# Sheet1.net
KiCad netlist of a schematic drawn in Altium Designer
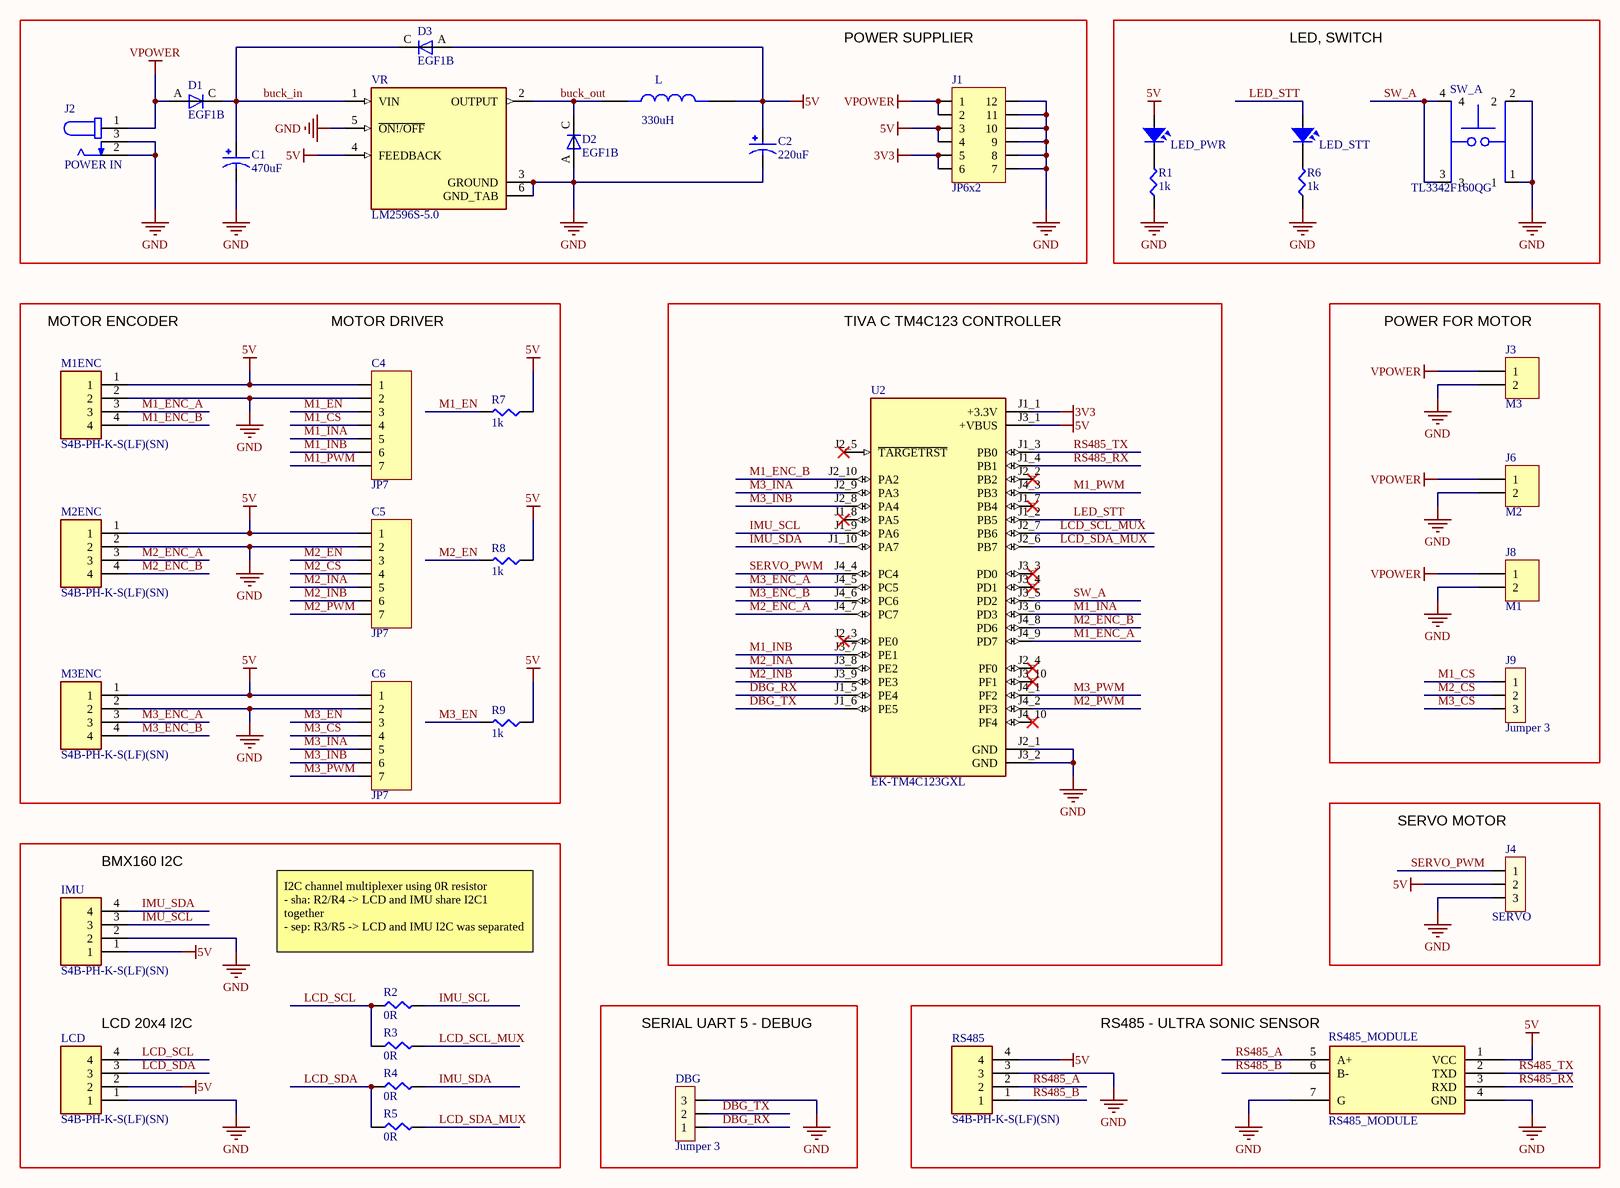
[diagram p0: Sheet1.SchDoc]

(export (version "E")
  (design (tool "Eeschema 10.0.6"))
  (components
    (comp (ref "C1")
      (value "470uF")
      (footprint "CAP_EEE2AA220P")
      (description "Capacitor; Alum Electrolytic; Cap 22 uF; Tol 20%; Vol-Rtg 100 VDC; SMT; 10x10.5; TR")
      (fields (field (name "MF") "Panasonic") (field (name "MP") "EEE-2AA220P"))
      (libsource (lib "EEE2AA220P") (part "EEE2AA220P"))
    )
    (comp (ref "C2")
      (value "220uF")
      (footprint "CAP_EEEHB1V220P")
      (description "EEE-HB Series 35 V 22 uF Ã˜ 6.3 x 5.8 mm 105 Â°C SMT V-Chip Aluminum Electrolytic")
      (fields (field (name "MP") "EEEHB1V220P") (field (name "MF") "Panasonic"))
      (libsource (lib "EEEHB1V220P") (part "EEEHB1V220P"))
    )
    (comp (ref "C4")
      (value "JP7")
      (footprint "JP7-C1T")
      (description "WR-PHD 2.54 mm Angled Socket Header")
      (fields
        (field (name "MANUFACTURER") "Würth Elektronik eiSos GmbH")
        (field (name "PARTNO") "613007143121")
        (field (name "CREATED BY") "Karrer Zheng")
      )
      (libsource (lib "My Library") (part "JP7_1"))
    )
    (comp (ref "C5")
      (value "JP7")
      (footprint "JP7-C1T")
      (description "WR-PHD 2.54 mm Angled Socket Header")
      (fields
        (field (name "MANUFACTURER") "Würth Elektronik eiSos GmbH")
        (field (name "PARTNO") "613007143121")
        (field (name "CREATED BY") "Karrer Zheng")
      )
      (libsource (lib "My Library") (part "JP7_1"))
    )
    (comp (ref "C6")
      (value "JP7")
      (footprint "JP7-C1T")
      (description "WR-PHD 2.54 mm Angled Socket Header")
      (fields
        (field (name "MANUFACTURER") "Würth Elektronik eiSos GmbH")
        (field (name "PARTNO") "613007143121")
        (field (name "CREATED BY") "Karrer Zheng")
      )
      (libsource (lib "My Library") (part "JP7_1"))
    )
    (comp (ref "D1")
      (value "EGF1B")
      (footprint "DIOM449X264X300L114X135N")
      (description "SS54 SMA\r\nDiode Shotky SS54 1N5824 5A 40V")
      (fields (field (name "MF") "ON Semiconductor"))
      (libsource (lib "EGF1B") (part "EGF1B"))
    )
    (comp (ref "D2")
      (value "EGF1B")
      (footprint "DIOM449X264X300L114X135N")
      (description "SS54 SMA\r\nDiode Shotky SS54 1N5824 5A 40V")
      (fields (field (name "MF") "ON Semiconductor"))
      (libsource (lib "EGF1B") (part "EGF1B"))
    )
    (comp (ref "D3")
      (value "EGF1B")
      (footprint "DIOM449X264X300L114X135N")
      (description "SS54 SMA\r\nDiode Shotky SS54 1N5824 5A 40V")
      (fields (field (name "MF") "ON Semiconductor"))
      (libsource (lib "EGF1B") (part "EGF1B"))
    )
    (comp (ref "DBG") (value "Jumper 3") (footprint "JP3") (libsource (lib "") (part "JP3_1")))
    (comp (ref "IMU")
      (value "S4B-PH-K-S(LF)(SN)")
      (footprint "JST_S4B-PH-K-S(LF)(SN)")
      (description "Connector Header Through Hole, Right Angle 4 position 0.079 _2.00mm_")
      (fields (field (name "MP") "S4B-PH-K-S_LF__SN_") (field (name "MF") "JST Sales"))
      (libsource (lib "S4B-PH-K-S_LF__SN_") (part "S4B-PH-K-S(LF)(SN)"))
    )
    (comp (ref "J1")
      (value "JP6x2")
      (footprint "JP6-D2T")
      (description "WR-PHD 2.54 mm Dual Socket Header")
      (fields
        (field (name "MANUFACTURER") "Würth Elektronik eiSos GmbH")
        (field (name "PARTNO") "61301221821")
        (field (name "CREATED BY") "Karrer Zheng")
      )
      (libsource (lib "My Library") (part "JP6x2"))
    )
    (comp (ref "J2")
      (value "POWER IN")
      (footprint "CUI_PJ-002B")
      (description "2.5 x 6.5 mm, 2.5 A, Horizontal, Through Hole, Dc Power Jack Connector")
      (fields (field (name "MF") "CUI Devices") (field (name "MP") "PJ-002B"))
      (libsource (lib "PJ-002B") (part "PJ-002B"))
    )
    (comp (ref "J3")
      (value "M3")
      (footprint "KF2-5.08")
      (fields
        (field (name "MANUFACTURER") "Würth Elektronik eiSos GmbH")
        (field (name "PARTNO") "691103110002")
        (field (name "CREATED BY") "Karrer Zheng")
      )
      (libsource (lib "My Library") (part "KF2"))
    )
    (comp (ref "J4") (value "SERVO") (footprint "JP3") (libsource (lib "My Library") (part "JP3")))
    (comp (ref "J6")
      (value "M2")
      (footprint "KF2-5.08")
      (fields
        (field (name "MANUFACTURER") "Würth Elektronik eiSos GmbH")
        (field (name "PARTNO") "691103110002")
        (field (name "CREATED BY") "Karrer Zheng")
      )
      (libsource (lib "My Library") (part "KF2"))
    )
    (comp (ref "J8")
      (value "M1")
      (footprint "KF2-5.08")
      (fields
        (field (name "MANUFACTURER") "Würth Elektronik eiSos GmbH")
        (field (name "PARTNO") "691103110002")
        (field (name "CREATED BY") "Karrer Zheng")
      )
      (libsource (lib "My Library") (part "KF2"))
    )
    (comp (ref "J9") (value "Jumper 3") (footprint "JP3") (libsource (lib "My Library") (part "JP3")))
    (comp (ref "L")
      (value "330uH")
      (footprint "IND_B1047AS-331M=P3")
      (description "Inductor with Inductance: 330uH Tol. +/-20%, Package: 2929 (7373)")
      (fields (field (name "MF") "Murata") (field (name "MP") "B1047AS-331M=P3"))
      (libsource (lib "B1047AS-331M_P3") (part "B1047AS-331M=P3"))
    )
    (comp (ref "LCD")
      (value "S4B-PH-K-S(LF)(SN)")
      (footprint "JST_S4B-PH-K-S(LF)(SN)")
      (description "Connector Header Through Hole, Right Angle 4 position 0.079 _2.00mm_")
      (fields (field (name "MP") "S4B-PH-K-S_LF__SN_") (field (name "MF") "JST Sales"))
      (libsource (lib "S4B-PH-K-S_LF__SN_") (part "S4B-PH-K-S(LF)(SN)"))
    )
    (comp (ref "LED_PWR")
      (value "PWR LED")
      (footprint "LED-0805-Green")
      (libsource (lib "My Library") (part "LED SMD"))
    )
    (comp (ref "LED_STT")
      (value "LED")
      (footprint "LED-0805-Green")
      (libsource (lib "My Library") (part "LED SMD"))
    )
    (comp (ref "M1ENC")
      (value "S4B-PH-K-S(LF)(SN)")
      (footprint "JST_S4B-PH-K-S(LF)(SN)")
      (description "Connector Header Through Hole, Right Angle 4 position 0.079 _2.00mm_")
      (fields (field (name "MP") "S4B-PH-K-S_LF__SN_") (field (name "MF") "JST Sales"))
      (libsource (lib "") (part "S4B-PH-K-S(LF)(SN)_1"))
    )
    (comp (ref "M2ENC")
      (value "S4B-PH-K-S(LF)(SN)")
      (footprint "JST_S4B-PH-K-S(LF)(SN)")
      (description "Connector Header Through Hole, Right Angle 4 position 0.079 _2.00mm_")
      (fields (field (name "MP") "S4B-PH-K-S_LF__SN_") (field (name "MF") "JST Sales"))
      (libsource (lib "") (part "S4B-PH-K-S(LF)(SN)_1"))
    )
    (comp (ref "M3ENC")
      (value "S4B-PH-K-S(LF)(SN)")
      (footprint "JST_S4B-PH-K-S(LF)(SN)")
      (description "Connector Header Through Hole, Right Angle 4 position 0.079 _2.00mm_")
      (fields (field (name "MP") "S4B-PH-K-S_LF__SN_") (field (name "MF") "JST Sales"))
      (libsource (lib "") (part "S4B-PH-K-S(LF)(SN)_1"))
    )
    (comp (ref "R1")
      (value "1k")
      (footprint "SMD-0805-RES")
      (description "RES SMD 0805")
      (fields (field (name "PART NUMBER") "ERJ-S6SJR20V") (field (name "DIGI-KEY PART NUMBER") "P.2BKCT-ND"))
      (libsource (lib "Panasonic_ERJ_0805") (part "Res SMD 0805"))
    )
    (comp (ref "R2")
      (value "0R")
      (footprint "SMD-0805-RES")
      (description "RES SMD 0805")
      (fields (field (name "PART NUMBER") "ERJ-S6SJR20V") (field (name "DIGI-KEY PART NUMBER") "P.2BKCT-ND"))
      (libsource (lib "Panasonic_ERJ_0805") (part "Res SMD 0805"))
    )
    (comp (ref "R3")
      (value "0R")
      (footprint "SMD-0805-RES")
      (description "RES SMD 0805")
      (fields (field (name "PART NUMBER") "ERJ-S6SJR20V") (field (name "DIGI-KEY PART NUMBER") "P.2BKCT-ND"))
      (libsource (lib "Panasonic_ERJ_0805") (part "Res SMD 0805"))
    )
    (comp (ref "R4")
      (value "0R")
      (footprint "SMD-0805-RES")
      (description "RES SMD 0805")
      (fields (field (name "PART NUMBER") "ERJ-S6SJR20V") (field (name "DIGI-KEY PART NUMBER") "P.2BKCT-ND"))
      (libsource (lib "Panasonic_ERJ_0805") (part "Res SMD 0805"))
    )
    (comp (ref "R5")
      (value "0R")
      (footprint "SMD-0805-RES")
      (description "RES SMD 0805")
      (fields (field (name "PART NUMBER") "ERJ-S6SJR20V") (field (name "DIGI-KEY PART NUMBER") "P.2BKCT-ND"))
      (libsource (lib "Panasonic_ERJ_0805") (part "Res SMD 0805"))
    )
    (comp (ref "R6")
      (value "1k")
      (footprint "SMD-0805-RES")
      (description "RES SMD 0805")
      (fields (field (name "PART NUMBER") "ERJ-S6SJR20V") (field (name "DIGI-KEY PART NUMBER") "P.2BKCT-ND"))
      (libsource (lib "Panasonic_ERJ_0805") (part "Res SMD 0805"))
    )
    (comp (ref "R7")
      (value "1k")
      (footprint "SMD-0805-RES")
      (description "RES SMD 0805")
      (fields (field (name "PART NUMBER") "ERJ-S6SJR20V") (field (name "DIGI-KEY PART NUMBER") "P.2BKCT-ND"))
      (libsource (lib "Panasonic_ERJ_0805") (part "Res SMD 0805"))
    )
    (comp (ref "R8")
      (value "1k")
      (footprint "SMD-0805-RES")
      (description "RES SMD 0805")
      (fields (field (name "PART NUMBER") "ERJ-S6SJR20V") (field (name "DIGI-KEY PART NUMBER") "P.2BKCT-ND"))
      (libsource (lib "Panasonic_ERJ_0805") (part "Res SMD 0805"))
    )
    (comp (ref "R9")
      (value "1k")
      (footprint "SMD-0805-RES")
      (description "RES SMD 0805")
      (fields (field (name "PART NUMBER") "ERJ-S6SJR20V") (field (name "DIGI-KEY PART NUMBER") "P.2BKCT-ND"))
      (libsource (lib "Panasonic_ERJ_0805") (part "Res SMD 0805"))
    )
    (comp (ref "RS485")
      (value "S4B-PH-K-S(LF)(SN)")
      (footprint "JST_S4B-PH-K-S(LF)(SN)")
      (description "Connector Header Through Hole, Right Angle 4 position 0.079 _2.00mm_")
      (fields (field (name "MP") "S4B-PH-K-S_LF__SN_") (field (name "MF") "JST Sales"))
      (libsource (lib "S4B-PH-K-S_LF__SN_") (part "S4B-PH-K-S(LF)(SN)"))
    )
    (comp (ref "RS485_MODULE")
      (value "RS485_MODULE")
      (footprint "RS485_MODULE")
      (libsource (lib "custom_lib") (part "RS485_MODULE"))
    )
    (comp (ref "SW_A")
      (value "TL3342F160QG")
      (footprint "SW_TL3342F160QG")
      (description "Tactile Switch SPST-NO Top Actuated Surface Mount")
      (fields (field (name "MF") "E-Switch"))
      (libsource (lib "TL3342F160QG") (part "TL3342F160QG"))
    )
    (comp (ref "U2")
      (value "EK-TM4C123GXL")
      (footprint "MODULE_EK-TM4C123GXL")
      (description "ARMÂ® CortexÂ®-M4F Based MCU TM4C123G LaunchPadâ„¢ Evaluation Kit")
      (fields (field (name "MF") "Texas Instruments"))
      (libsource (lib "EK-TM4C123GXL") (part "EK-TM4C123GXL"))
    )
    (comp (ref "VR")
      (value "LM2596S-5.0")
      (footprint "TO170P1524X483-6N")
      (description "SIMPLE SWITCHER&reg; 4.5V to 40V, 3A Low Component Count Step-Down Regulator 5-DDPAK/TO-263")
      (fields (field (name "MF") "Texas Instruments") (field (name "MP") "LM2596S-5.0/NOPB"))
      (libsource (lib "LM2596S-5.0") (part "LM2596S-5.0"))
    )
  )
  (nets
    (net (code "1") (name "/DBG_RX") (class "Default")
      (node (ref "DBG") (pin "1") (pinfunction "1_1") (pintype "passive"))
      (node (ref "U2") (pin "J1_5") (pinfunction "PE4_J1_5") (pintype "bidirectional"))
    )
    (net (code "2") (name "/DBG_TX") (class "Default")
      (node (ref "DBG") (pin "2") (pinfunction "2_2") (pintype "passive"))
      (node (ref "U2") (pin "J1_6") (pinfunction "PE5_J1_6") (pintype "bidirectional"))
    )
    (net (code "3") (name "/IMU_SCL") (class "Default")
      (node (ref "IMU") (pin "3") (pinfunction "3_3") (pintype "passive"))
      (node (ref "R2") (pin "2") (pinfunction "2_2") (pintype "passive"))
      (node (ref "U2") (pin "J1_9") (pinfunction "PA6_J1_9") (pintype "bidirectional"))
    )
    (net (code "4") (name "/IMU_SDA") (class "Default")
      (node (ref "IMU") (pin "4") (pinfunction "4_4") (pintype "passive"))
      (node (ref "R4") (pin "2") (pinfunction "2_2") (pintype "passive"))
      (node (ref "U2") (pin "J1_10") (pinfunction "PA7_J1_10") (pintype "bidirectional"))
    )
    (net (code "5") (name "/LCD_SCL") (class "Default")
      (node (ref "LCD") (pin "4") (pinfunction "4_4") (pintype "passive"))
      (node (ref "R2") (pin "1") (pinfunction "1_1") (pintype "passive"))
      (node (ref "R3") (pin "1") (pinfunction "1_1") (pintype "passive"))
    )
    (net (code "6") (name "/LCD_SCL_MUX") (class "Default")
      (node (ref "R3") (pin "2") (pinfunction "2_2") (pintype "passive"))
      (node (ref "U2") (pin "J2_7") (pinfunction "PB6_J2_7") (pintype "bidirectional"))
    )
    (net (code "7") (name "/LCD_SDA") (class "Default")
      (node (ref "LCD") (pin "3") (pinfunction "3_3") (pintype "passive"))
      (node (ref "R4") (pin "1") (pinfunction "1_1") (pintype "passive"))
      (node (ref "R5") (pin "1") (pinfunction "1_1") (pintype "passive"))
    )
    (net (code "8") (name "/LCD_SDA_MUX") (class "Default")
      (node (ref "R5") (pin "2") (pinfunction "2_2") (pintype "passive"))
      (node (ref "U2") (pin "J2_6") (pinfunction "PB7_J2_6") (pintype "bidirectional"))
    )
    (net (code "9") (name "/LED_STT") (class "Default")
      (node (ref "LED_STT") (pin "1") (pinfunction "1_1") (pintype "passive"))
      (node (ref "U2") (pin "J1_2") (pinfunction "PB5_J1_2") (pintype "bidirectional"))
    )
    (net (code "10") (name "/M1_CS") (class "Default")
      (node (ref "C4") (pin "4") (pinfunction "4_4") (pintype "passive"))
      (node (ref "J9") (pin "1") (pinfunction "1_1") (pintype "passive"))
    )
    (net (code "11") (name "/M1_EN") (class "Default")
      (node (ref "C4") (pin "3") (pinfunction "3_3") (pintype "passive"))
      (node (ref "R7") (pin "2") (pinfunction "2_2") (pintype "passive"))
    )
    (net (code "12") (name "/M1_ENC_A") (class "Default")
      (node (ref "M1ENC") (pin "3") (pinfunction "3_3") (pintype "passive"))
      (node (ref "U2") (pin "J4_9") (pinfunction "PD7_J4_9") (pintype "bidirectional"))
    )
    (net (code "13") (name "/M1_ENC_B") (class "Default")
      (node (ref "M1ENC") (pin "4") (pinfunction "4_4") (pintype "passive"))
      (node (ref "U2") (pin "J2_10") (pinfunction "PA2_J2_10") (pintype "bidirectional"))
    )
    (net (code "14") (name "/M1_INA") (class "Default")
      (node (ref "C4") (pin "5") (pinfunction "5_5") (pintype "passive"))
      (node (ref "U2") (pin "J3_6") (pinfunction "PD3_J3_6") (pintype "bidirectional"))
    )
    (net (code "15") (name "/M1_INB") (class "Default")
      (node (ref "C4") (pin "6") (pinfunction "6_6") (pintype "passive"))
      (node (ref "U2") (pin "J3_7") (pinfunction "PE1_J3_7") (pintype "bidirectional"))
    )
    (net (code "16") (name "/M1_PWM") (class "Default")
      (node (ref "C4") (pin "7") (pinfunction "7_7") (pintype "passive"))
      (node (ref "U2") (pin "J4_3") (pinfunction "PB3_J4_3") (pintype "bidirectional"))
    )
    (net (code "17") (name "/M2_CS") (class "Default")
      (node (ref "C5") (pin "4") (pinfunction "4_4") (pintype "passive"))
      (node (ref "J9") (pin "2") (pinfunction "2_2") (pintype "passive"))
    )
    (net (code "18") (name "/M2_EN") (class "Default")
      (node (ref "C5") (pin "3") (pinfunction "3_3") (pintype "passive"))
      (node (ref "R8") (pin "2") (pinfunction "2_2") (pintype "passive"))
    )
    (net (code "19") (name "/M2_ENC_A") (class "Default")
      (node (ref "M2ENC") (pin "3") (pinfunction "3_3") (pintype "passive"))
      (node (ref "U2") (pin "J4_7") (pinfunction "PC7_J4_7") (pintype "bidirectional"))
    )
    (net (code "20") (name "/M2_ENC_B") (class "Default")
      (node (ref "M2ENC") (pin "4") (pinfunction "4_4") (pintype "passive"))
      (node (ref "U2") (pin "J4_8") (pinfunction "PD6_J4_8") (pintype "bidirectional"))
    )
    (net (code "21") (name "/M2_INA") (class "Default")
      (node (ref "C5") (pin "5") (pinfunction "5_5") (pintype "passive"))
      (node (ref "U2") (pin "J3_8") (pinfunction "PE2_J3_8") (pintype "bidirectional"))
    )
    (net (code "22") (name "/M2_INB") (class "Default")
      (node (ref "C5") (pin "6") (pinfunction "6_6") (pintype "passive"))
      (node (ref "U2") (pin "J3_9") (pinfunction "PE3_J3_9") (pintype "bidirectional"))
    )
    (net (code "23") (name "/M2_PWM") (class "Default")
      (node (ref "C5") (pin "7") (pinfunction "7_7") (pintype "passive"))
      (node (ref "U2") (pin "J4_2") (pinfunction "PF3_J4_2") (pintype "bidirectional"))
    )
    (net (code "24") (name "/M3_CS") (class "Default")
      (node (ref "C6") (pin "4") (pinfunction "4_4") (pintype "passive"))
      (node (ref "J9") (pin "3") (pinfunction "3_3") (pintype "passive"))
    )
    (net (code "25") (name "/M3_EN") (class "Default")
      (node (ref "C6") (pin "3") (pinfunction "3_3") (pintype "passive"))
      (node (ref "R9") (pin "2") (pinfunction "2_2") (pintype "passive"))
    )
    (net (code "26") (name "/M3_ENC_A") (class "Default")
      (node (ref "M3ENC") (pin "3") (pinfunction "3_3") (pintype "passive"))
      (node (ref "U2") (pin "J4_5") (pinfunction "PC5_J4_5") (pintype "bidirectional"))
    )
    (net (code "27") (name "/M3_ENC_B") (class "Default")
      (node (ref "M3ENC") (pin "4") (pinfunction "4_4") (pintype "passive"))
      (node (ref "U2") (pin "J4_6") (pinfunction "PC6_J4_6") (pintype "bidirectional"))
    )
    (net (code "28") (name "/M3_INA") (class "Default")
      (node (ref "C6") (pin "5") (pinfunction "5_5") (pintype "passive"))
      (node (ref "U2") (pin "J2_9") (pinfunction "PA3_J2_9") (pintype "bidirectional"))
    )
    (net (code "29") (name "/M3_INB") (class "Default")
      (node (ref "C6") (pin "6") (pinfunction "6_6") (pintype "passive"))
      (node (ref "U2") (pin "J2_8") (pinfunction "PA4_J2_8") (pintype "bidirectional"))
    )
    (net (code "30") (name "/M3_PWM") (class "Default")
      (node (ref "C6") (pin "7") (pinfunction "7_7") (pintype "passive"))
      (node (ref "U2") (pin "J4_1") (pinfunction "PF2_J4_1") (pintype "bidirectional"))
    )
    (net (code "31") (name "/RS485_A") (class "Default")
      (node (ref "RS485") (pin "2") (pinfunction "2_2") (pintype "passive"))
      (node (ref "RS485_MODULE") (pin "5") (pinfunction "A+_5") (pintype "passive"))
    )
    (net (code "32") (name "/RS485_B") (class "Default")
      (node (ref "RS485") (pin "1") (pinfunction "1_1") (pintype "passive"))
      (node (ref "RS485_MODULE") (pin "6") (pinfunction "B-_6") (pintype "passive"))
    )
    (net (code "33") (name "/RS485_RX") (class "Default")
      (node (ref "RS485_MODULE") (pin "3") (pinfunction "RXD_3") (pintype "passive"))
      (node (ref "U2") (pin "J1_4") (pinfunction "PB1_J1_4") (pintype "bidirectional"))
    )
    (net (code "34") (name "/RS485_TX") (class "Default")
      (node (ref "RS485_MODULE") (pin "2") (pinfunction "TXD_2") (pintype "passive"))
      (node (ref "U2") (pin "J1_3") (pinfunction "PB0_J1_3") (pintype "bidirectional"))
    )
    (net (code "35") (name "/SERVO_PWM") (class "Default")
      (node (ref "J4") (pin "1") (pinfunction "1_1") (pintype "passive"))
      (node (ref "U2") (pin "J4_4") (pinfunction "PC4_J4_4") (pintype "bidirectional"))
    )
    (net (code "36") (name "/SW_A") (class "Default")
      (node (ref "SW_A") (pin "3") (pinfunction "3_3") (pintype "passive"))
      (node (ref "SW_A") (pin "4") (pinfunction "4_4") (pintype "passive"))
      (node (ref "U2") (pin "J3_5") (pinfunction "PD2_J3_5") (pintype "bidirectional"))
    )
    (net (code "37") (name "/buck_in") (class "Default")
      (node (ref "C1") (pin "1") (pinfunction "1_1") (pintype "passive"))
      (node (ref "D1") (pin "C") (pinfunction "C_C") (pintype "passive"))
      (node (ref "D3") (pin "C") (pinfunction "C_C") (pintype "passive"))
      (node (ref "VR") (pin "1") (pinfunction "VIN_1") (pintype "input"))
    )
    (net (code "38") (name "/buck_out") (class "Default")
      (node (ref "D2") (pin "C") (pinfunction "C_C") (pintype "passive"))
      (node (ref "L") (pin "1") (pinfunction "1_1") (pintype "passive"))
      (node (ref "VR") (pin "2") (pinfunction "OUTPUT_2") (pintype "output"))
    )
    (net (code "39") (name "3V3") (class "Default")
      (node (ref "J1") (pin "5") (pinfunction "5_5") (pintype "passive"))
      (node (ref "J1") (pin "6") (pinfunction "6_6") (pintype "passive"))
      (node (ref "U2") (pin "J1_1") (pinfunction "+3.3V_J1_1") (pintype "power_in"))
    )
    (net (code "40") (name "5V") (class "Default")
      (node (ref "C2") (pin "1") (pinfunction "1_1") (pintype "passive"))
      (node (ref "C4") (pin "1") (pinfunction "1_1") (pintype "passive"))
      (node (ref "C5") (pin "1") (pinfunction "1_1") (pintype "passive"))
      (node (ref "C6") (pin "1") (pinfunction "1_1") (pintype "passive"))
      (node (ref "D3") (pin "A") (pinfunction "A_A") (pintype "passive"))
      (node (ref "IMU") (pin "1") (pinfunction "1_1") (pintype "passive"))
      (node (ref "J1") (pin "3") (pinfunction "3_3") (pintype "passive"))
      (node (ref "J1") (pin "4") (pinfunction "4_4") (pintype "passive"))
      (node (ref "J4") (pin "2") (pinfunction "2_2") (pintype "passive"))
      (node (ref "L") (pin "2") (pinfunction "2_2") (pintype "passive"))
      (node (ref "LCD") (pin "2") (pinfunction "2_2") (pintype "passive"))
      (node (ref "LED_PWR") (pin "1") (pinfunction "1_1") (pintype "passive"))
      (node (ref "M1ENC") (pin "1") (pinfunction "1_1") (pintype "passive"))
      (node (ref "M2ENC") (pin "1") (pinfunction "1_1") (pintype "passive"))
      (node (ref "M3ENC") (pin "1") (pinfunction "1_1") (pintype "passive"))
      (node (ref "R7") (pin "1") (pinfunction "1_1") (pintype "passive"))
      (node (ref "R8") (pin "1") (pinfunction "1_1") (pintype "passive"))
      (node (ref "R9") (pin "1") (pinfunction "1_1") (pintype "passive"))
      (node (ref "RS485") (pin "4") (pinfunction "4_4") (pintype "passive"))
      (node (ref "RS485_MODULE") (pin "1") (pinfunction "VCC_1") (pintype "passive"))
      (node (ref "U2") (pin "J3_1") (pinfunction "+VBUS_J3_1") (pintype "power_in"))
      (node (ref "VR") (pin "4") (pinfunction "FEEDBACK_4") (pintype "input"))
    )
    (net (code "41") (name "GND") (class "Default")
      (node (ref "C1") (pin "2") (pinfunction "2_2") (pintype "passive"))
      (node (ref "C2") (pin "2") (pinfunction "2_2") (pintype "passive"))
      (node (ref "C4") (pin "2") (pinfunction "2_2") (pintype "passive"))
      (node (ref "C5") (pin "2") (pinfunction "2_2") (pintype "passive"))
      (node (ref "C6") (pin "2") (pinfunction "2_2") (pintype "passive"))
      (node (ref "D2") (pin "A") (pinfunction "A_A") (pintype "passive"))
      (node (ref "DBG") (pin "3") (pinfunction "3_3") (pintype "passive"))
      (node (ref "IMU") (pin "2") (pinfunction "2_2") (pintype "passive"))
      (node (ref "J1") (pin "10") (pinfunction "10_10") (pintype "passive"))
      (node (ref "J1") (pin "11") (pinfunction "11_11") (pintype "passive"))
      (node (ref "J1") (pin "12") (pinfunction "12_12") (pintype "passive"))
      (node (ref "J1") (pin "7") (pinfunction "7_7") (pintype "passive"))
      (node (ref "J1") (pin "8") (pinfunction "8_8") (pintype "passive"))
      (node (ref "J1") (pin "9") (pinfunction "9_9") (pintype "passive"))
      (node (ref "J2") (pin "2") (pinfunction "2_2") (pintype "passive"))
      (node (ref "J2") (pin "3") (pinfunction "3_3") (pintype "passive"))
      (node (ref "J3") (pin "2") (pinfunction "2_2") (pintype "passive"))
      (node (ref "J4") (pin "3") (pinfunction "3_3") (pintype "passive"))
      (node (ref "J6") (pin "2") (pinfunction "2_2") (pintype "passive"))
      (node (ref "J8") (pin "2") (pinfunction "2_2") (pintype "passive"))
      (node (ref "LCD") (pin "1") (pinfunction "1_1") (pintype "passive"))
      (node (ref "M1ENC") (pin "2") (pinfunction "2_2") (pintype "passive"))
      (node (ref "M2ENC") (pin "2") (pinfunction "2_2") (pintype "passive"))
      (node (ref "M3ENC") (pin "2") (pinfunction "2_2") (pintype "passive"))
      (node (ref "R1") (pin "1") (pinfunction "1_1") (pintype "passive"))
      (node (ref "R6") (pin "1") (pinfunction "1_1") (pintype "passive"))
      (node (ref "RS485") (pin "3") (pinfunction "3_3") (pintype "passive"))
      (node (ref "RS485_MODULE") (pin "4") (pinfunction "GND_4") (pintype "passive"))
      (node (ref "RS485_MODULE") (pin "7") (pinfunction "G_7") (pintype "passive"))
      (node (ref "SW_A") (pin "1") (pinfunction "1_1") (pintype "passive"))
      (node (ref "SW_A") (pin "2") (pinfunction "2_2") (pintype "passive"))
      (node (ref "U2") (pin "J2_1") (pinfunction "GND_J2_1") (pintype "power_in"))
      (node (ref "U2") (pin "J3_2") (pinfunction "GND_J3_2") (pintype "power_in"))
      (node (ref "VR") (pin "3") (pinfunction "GROUND_3") (pintype "power_in"))
      (node (ref "VR") (pin "5") (pinfunction "~{ON!/OFF}_5") (pintype "input"))
      (node (ref "VR") (pin "6") (pinfunction "GND_TAB_6") (pintype "power_in"))
    )
    (net (code "42") (name "Net-(LED_PWR-Pad2)") (class "Default")
      (node (ref "LED_PWR") (pin "2") (pinfunction "2_2") (pintype "passive"))
      (node (ref "R1") (pin "2") (pinfunction "2_2") (pintype "passive"))
    )
    (net (code "43") (name "Net-(LED_STT-Pad2)") (class "Default")
      (node (ref "LED_STT") (pin "2") (pinfunction "2_2") (pintype "passive"))
      (node (ref "R6") (pin "2") (pinfunction "2_2") (pintype "passive"))
    )
    (net (code "44") (name "VPOWER") (class "Default")
      (node (ref "D1") (pin "A") (pinfunction "A_A") (pintype "passive"))
      (node (ref "J1") (pin "1") (pinfunction "1_1") (pintype "passive"))
      (node (ref "J1") (pin "2") (pinfunction "2_2") (pintype "passive"))
      (node (ref "J2") (pin "1") (pinfunction "1_1") (pintype "passive"))
      (node (ref "J3") (pin "1") (pinfunction "1_1") (pintype "passive"))
      (node (ref "J6") (pin "1") (pinfunction "1_1") (pintype "passive"))
      (node (ref "J8") (pin "1") (pinfunction "1_1") (pintype "passive"))
    )
    (net (code "45") (name "unconnected-(U2-PA5-PadJ1_8)") (class "Default")
      (node (ref "U2") (pin "J1_8") (pinfunction "PA5_J1_8") (pintype "bidirectional+no_connect"))
    )
    (net (code "46") (name "unconnected-(U2-PB2-PadJ2_2)") (class "Default")
      (node (ref "U2") (pin "J2_2") (pinfunction "PB2_J2_2") (pintype "bidirectional+no_connect"))
    )
    (net (code "47") (name "unconnected-(U2-PB4-PadJ1_7)") (class "Default")
      (node (ref "U2") (pin "J1_7") (pinfunction "PB4_J1_7") (pintype "bidirectional+no_connect"))
    )
    (net (code "48") (name "unconnected-(U2-PD0-PadJ3_3)") (class "Default")
      (node (ref "U2") (pin "J3_3") (pinfunction "PD0_J3_3") (pintype "bidirectional+no_connect"))
    )
    (net (code "49") (name "unconnected-(U2-PD1-PadJ3_4)") (class "Default")
      (node (ref "U2") (pin "J3_4") (pinfunction "PD1_J3_4") (pintype "bidirectional+no_connect"))
    )
    (net (code "50") (name "unconnected-(U2-PE0-PadJ2_3)") (class "Default")
      (node (ref "U2") (pin "J2_3") (pinfunction "PE0_J2_3") (pintype "bidirectional+no_connect"))
    )
    (net (code "51") (name "unconnected-(U2-PF0-PadJ2_4)") (class "Default")
      (node (ref "U2") (pin "J2_4") (pinfunction "PF0_J2_4") (pintype "bidirectional+no_connect"))
    )
    (net (code "52") (name "unconnected-(U2-PF1-PadJ3_10)") (class "Default")
      (node (ref "U2") (pin "J3_10") (pinfunction "PF1_J3_10") (pintype "bidirectional+no_connect"))
    )
    (net (code "53") (name "unconnected-(U2-PF4-PadJ4_10)") (class "Default")
      (node (ref "U2") (pin "J4_10") (pinfunction "PF4_J4_10") (pintype "bidirectional+no_connect"))
    )
    (net (code "54") (name "unconnected-(U2-~{TARGETRST}-PadJ2_5)") (class "Default")
      (node (ref "U2") (pin "J2_5") (pinfunction "~{TARGETRST}_J2_5") (pintype "input+no_connect"))
    )
  )
)
